# 02_Connectors.net
KiCad netlist of a schematic drawn in Altium Designer
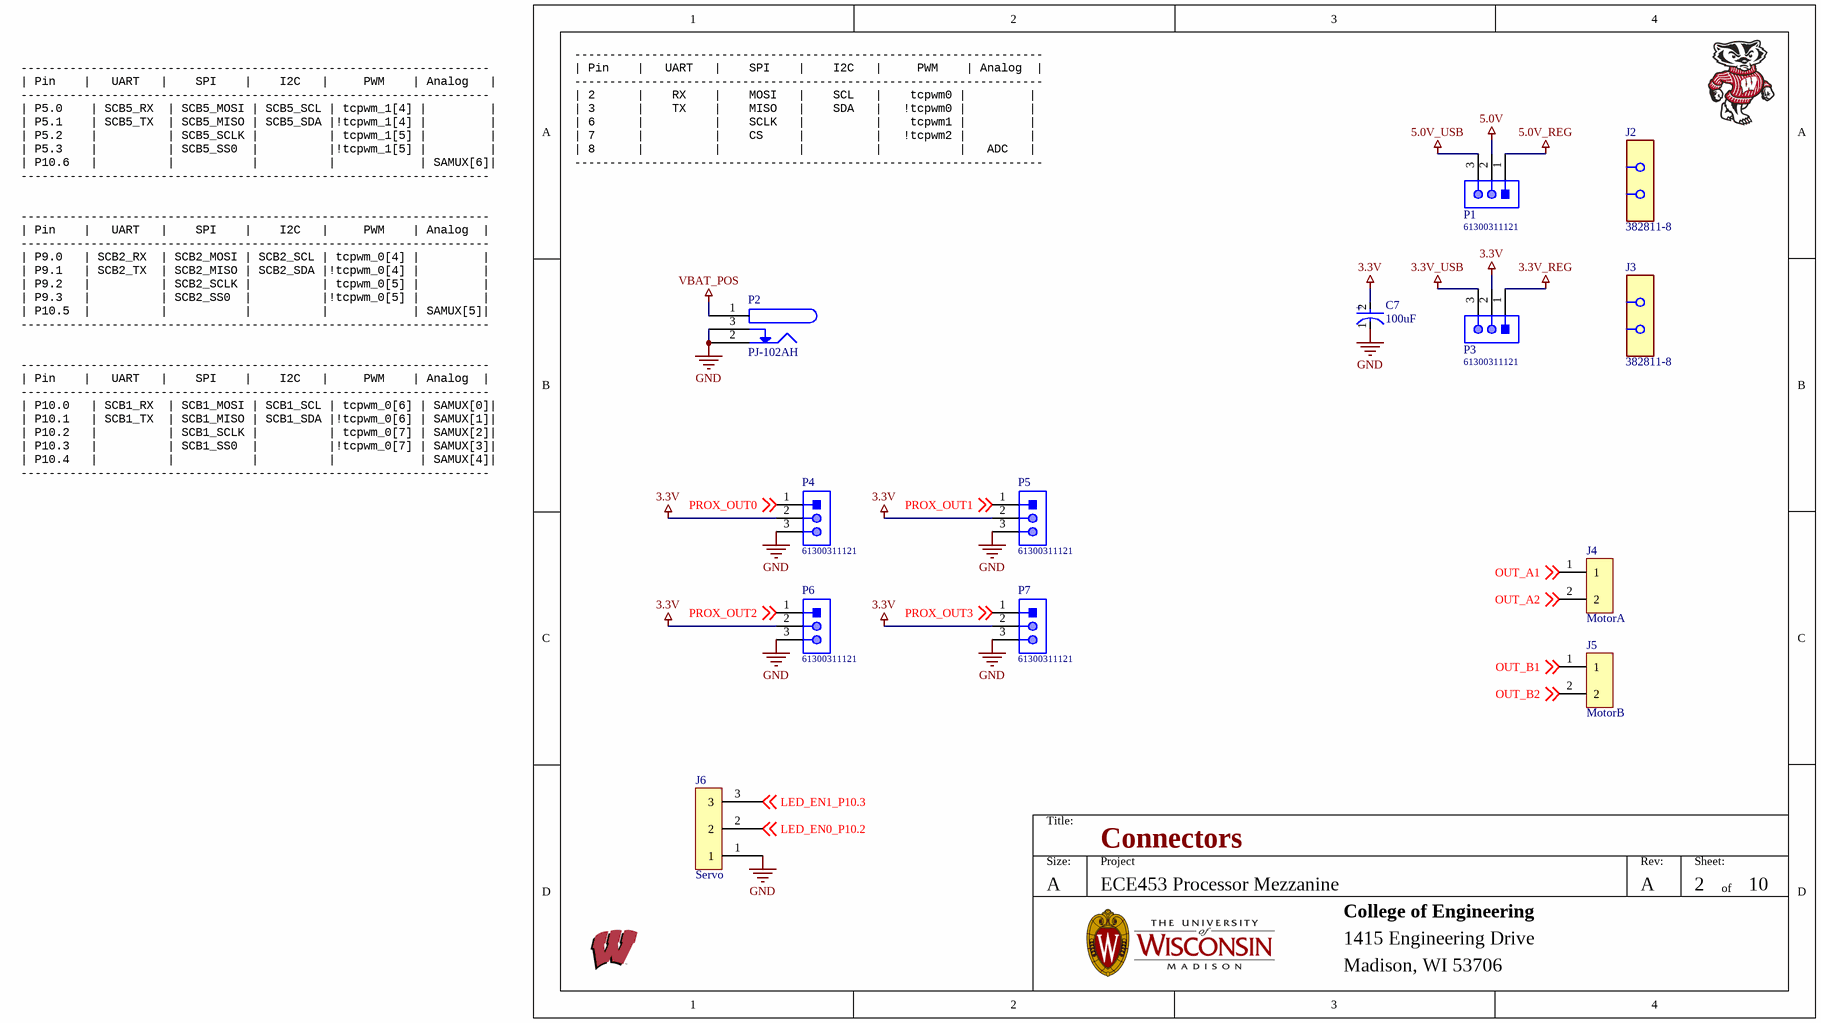
[diagram p0: 02_Connectors.SchDoc]

(export (version "E")
  (design (tool "Eeschema 10.0.6"))
  (components
    (comp (ref "C7")
      (value "EEE-1EA101XP")
      (footprint "FP-SD8-MFG")
      (description "CAP ALUM 100UF 20% 25V SMD")
      (fields
        (field (name "VOLTAGE") "25V")
        (field (name "TOLERANCE") "20%")
        (field (name "CAPACITANCE") "100uF")
      )
      (libsource (lib "ECE453") (part "CMP-05427-000061-1"))
    )
    (comp (ref "J2")
      (value "382811-8")
      (footprint "FP-382811-8-MFG")
      (description "CONN SHUNT 2POS OPEN 2.54MM")
      (fields (field (name "MANUFACTURER") "TE Connectivity"))
      (libsource (lib "ECE453") (part "CMP-03355-000020-1"))
    )
    (comp (ref "J3")
      (value "382811-8")
      (footprint "FP-382811-8-MFG")
      (description "CONN SHUNT 2POS OPEN 2.54MM")
      (fields (field (name "MANUFACTURER") "TE Connectivity"))
      (libsource (lib "ECE453") (part "CMP-03355-000020-1"))
    )
    (comp (ref "J4")
      (value "MotorA")
      (footprint "PHOENIX2X0.2")
      (description "2~24 Poles, Screw Type, Horizontal, 5.08 Pitch, 26~14 (AWG), Terminal Block Connector")
      (fields
        (field (name "MANUFACTURER") "CUI Devices")
        (field (name "MANUFACTURER PART NUMBER") "TB006-508-02BE")
      )
      (libsource (lib "ECE453") (part "2-Pin"))
    )
    (comp (ref "J5")
      (value "MotorB")
      (footprint "PHOENIX2X0.2")
      (description "2~24 Poles, Screw Type, Horizontal, 5.08 Pitch, 26~14 (AWG), Terminal Block Connector")
      (fields
        (field (name "MANUFACTURER") "CUI Devices")
        (field (name "MANUFACTURER PART NUMBER") "TB006-508-02BE")
      )
      (libsource (lib "ECE453") (part "2-Pin"))
    )
    (comp (ref "J6")
      (value "Servo")
      (footprint "PHOENIX3X0.2")
      (description "2~24 Poles, Screw Type, Horizontal, 5.08 Pitch, 26~14 (AWG), Terminal Block Connector")
      (fields
        (field (name "MANUFACTURER") "CUI Devices")
        (field (name "MANUFACTURER PART NUMBER") "TB006-508-03BE")
      )
      (libsource (lib "ECE453") (part "3-Pin_2"))
    )
    (comp (ref "P1")
      (value "61300311121")
      (footprint "61300311121")
      (description "THT Vertical Pin Header WR-PHD, Pitch 2.54 mm, Single Row, 3 pins")
      (fields (field (name "MANUFACTURER") "Wurth Elektronik") (field (name "PUBLISHER") "WurthElektronik"))
      (libsource (lib "") (part "CMP-1502-01062-1_1"))
    )
    (comp (ref "P2")
      (value "PJ-102")
      (footprint "PJ-102")
      (description "CONN PWR JACK 2.1X5.5MM HIGH CUR")
      (fields (field (name "MANUFACTURER") "CUI Inc") (field (name "MANUFACTURER PART NUMBER") "PJ-102AH"))
      (libsource (lib "ECE453") (part "CONN JACK PWR W/SW"))
    )
    (comp (ref "P3")
      (value "61300311121")
      (footprint "61300311121")
      (description "THT Vertical Pin Header WR-PHD, Pitch 2.54 mm, Single Row, 3 pins")
      (fields (field (name "MANUFACTURER") "Wurth Elektronik") (field (name "PUBLISHER") "WurthElektronik"))
      (libsource (lib "") (part "CMP-1502-01062-1_1"))
    )
    (comp (ref "P4")
      (value "61300311121")
      (footprint "61300311121")
      (description "THT Vertical Pin Header WR-PHD, Pitch 2.54 mm, Single Row, 3 pins")
      (fields (field (name "MANUFACTURER") "Wurth Elektronik") (field (name "PUBLISHER") "WurthElektronik"))
      (libsource (lib "ECE453") (part "CMP-1502-01062-1"))
    )
    (comp (ref "P5")
      (value "61300311121")
      (footprint "61300311121")
      (description "THT Vertical Pin Header WR-PHD, Pitch 2.54 mm, Single Row, 3 pins")
      (fields (field (name "MANUFACTURER") "Wurth Elektronik") (field (name "PUBLISHER") "WurthElektronik"))
      (libsource (lib "ECE453") (part "CMP-1502-01062-1"))
    )
    (comp (ref "P6")
      (value "61300311121")
      (footprint "61300311121")
      (description "THT Vertical Pin Header WR-PHD, Pitch 2.54 mm, Single Row, 3 pins")
      (fields (field (name "MANUFACTURER") "Wurth Elektronik") (field (name "PUBLISHER") "WurthElektronik"))
      (libsource (lib "ECE453") (part "CMP-1502-01062-1"))
    )
    (comp (ref "P7")
      (value "61300311121")
      (footprint "61300311121")
      (description "THT Vertical Pin Header WR-PHD, Pitch 2.54 mm, Single Row, 3 pins")
      (fields (field (name "MANUFACTURER") "Wurth Elektronik") (field (name "PUBLISHER") "WurthElektronik"))
      (libsource (lib "ECE453") (part "CMP-1502-01062-1"))
    )
  )
  (nets
    (net (code "1") (name "3.3V") (class "Default")
      (node (ref "C7") (pin "2") (pinfunction "A_2") (pintype "passive"))
      (node (ref "P3") (pin "2") (pinfunction "2_2") (pintype "passive"))
      (node (ref "P4") (pin "2") (pinfunction "2_2") (pintype "passive"))
      (node (ref "P5") (pin "2") (pinfunction "2_2") (pintype "passive"))
      (node (ref "P6") (pin "2") (pinfunction "2_2") (pintype "passive"))
      (node (ref "P7") (pin "2") (pinfunction "2_2") (pintype "passive"))
    )
    (net (code "2") (name "3.3V_REG") (class "Default")
      (node (ref "P3") (pin "1") (pinfunction "1_1") (pintype "passive"))
    )
    (net (code "3") (name "3.3V_USB") (class "Default")
      (node (ref "P3") (pin "3") (pinfunction "3_3") (pintype "passive"))
    )
    (net (code "4") (name "5.0V") (class "Default")
      (node (ref "P1") (pin "2") (pinfunction "2_2") (pintype "passive"))
    )
    (net (code "5") (name "5.0V_REG") (class "Default")
      (node (ref "P1") (pin "1") (pinfunction "1_1") (pintype "passive"))
    )
    (net (code "6") (name "5.0V_USB") (class "Default")
      (node (ref "P1") (pin "3") (pinfunction "3_3") (pintype "passive"))
    )
    (net (code "7") (name "GND") (class "Default")
      (node (ref "C7") (pin "1") (pinfunction "C_1") (pintype "passive"))
      (node (ref "J6") (pin "1") (pinfunction "1_1") (pintype "passive"))
      (node (ref "P2") (pin "2") (pinfunction "2_2") (pintype "passive"))
      (node (ref "P2") (pin "3") (pinfunction "3_3") (pintype "passive"))
      (node (ref "P4") (pin "3") (pinfunction "3_3") (pintype "passive"))
      (node (ref "P5") (pin "3") (pinfunction "3_3") (pintype "passive"))
      (node (ref "P6") (pin "3") (pinfunction "3_3") (pintype "passive"))
      (node (ref "P7") (pin "3") (pinfunction "3_3") (pintype "passive"))
    )
    (net (code "8") (name "LED_EN0_P10.2") (class "Default")
      (node (ref "J6") (pin "2") (pinfunction "2_2") (pintype "passive"))
    )
    (net (code "9") (name "LED_EN1_P10.3") (class "Default")
      (node (ref "J6") (pin "3") (pinfunction "3_3") (pintype "passive"))
    )
    (net (code "10") (name "OUT_A1") (class "Default")
      (node (ref "J4") (pin "1") (pinfunction "1_1") (pintype "passive"))
    )
    (net (code "11") (name "OUT_A2") (class "Default")
      (node (ref "J4") (pin "2") (pinfunction "2_2") (pintype "passive"))
    )
    (net (code "12") (name "OUT_B1") (class "Default")
      (node (ref "J5") (pin "1") (pinfunction "1_1") (pintype "passive"))
    )
    (net (code "13") (name "OUT_B2") (class "Default")
      (node (ref "J5") (pin "2") (pinfunction "2_2") (pintype "passive"))
    )
    (net (code "14") (name "PROX_OUT0") (class "Default")
      (node (ref "P4") (pin "1") (pinfunction "1_1") (pintype "passive"))
    )
    (net (code "15") (name "PROX_OUT1") (class "Default")
      (node (ref "P5") (pin "1") (pinfunction "1_1") (pintype "passive"))
    )
    (net (code "16") (name "PROX_OUT2") (class "Default")
      (node (ref "P6") (pin "1") (pinfunction "1_1") (pintype "passive"))
    )
    (net (code "17") (name "PROX_OUT3") (class "Default")
      (node (ref "P7") (pin "1") (pinfunction "1_1") (pintype "passive"))
    )
    (net (code "18") (name "VBAT_POS") (class "Default")
      (node (ref "P2") (pin "1") (pinfunction "1_1") (pintype "passive"))
    )
  )
)
